# usb.net
KiCad netlist of a schematic drawn in Altium Designer
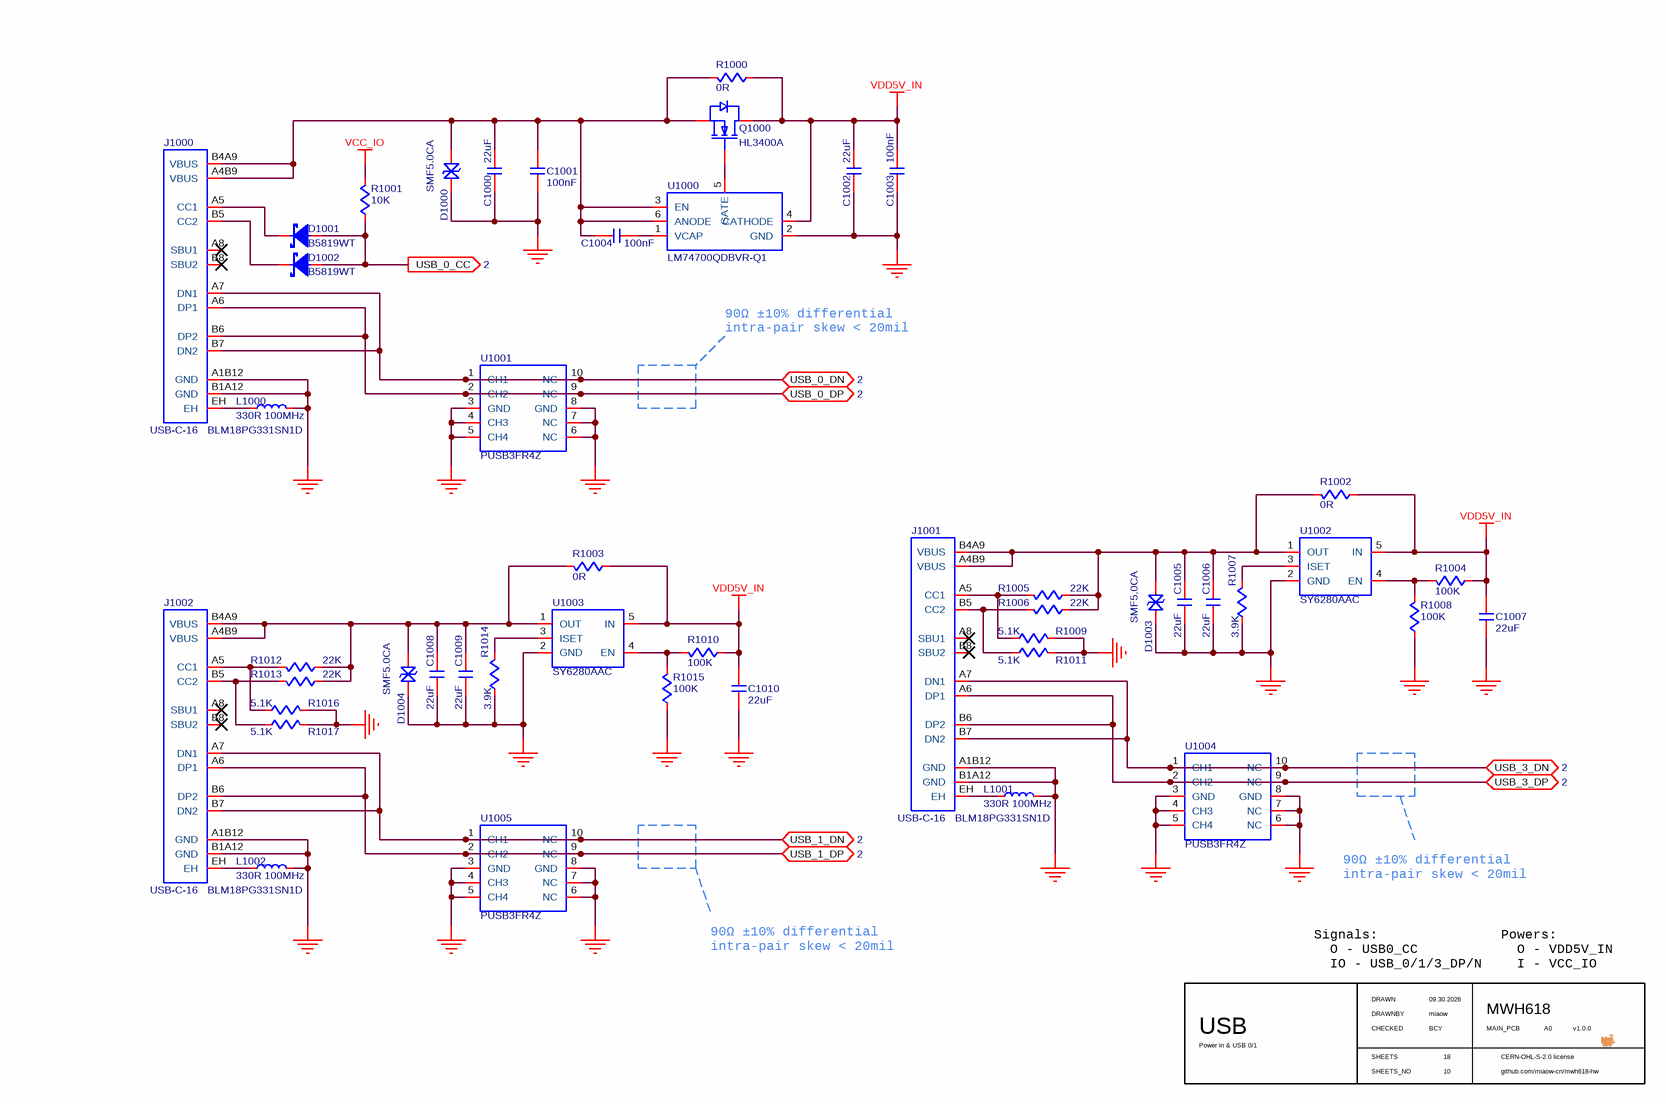
[diagram p0: usb.schdoc]

(export (version "E")
  (design (tool "Eeschema 10.0.6"))
  (components
    (comp (ref "C1000")
      (value "22uF")
      (footprint "mw:C0603")
      (fields (field (name "VOLTAGE") "10V") (field (name "Comment") "C-NOMO"))
      (libsource (lib "mw") (part "C-NOMO"))
    )
    (comp (ref "C1001")
      (value "100nF")
      (footprint "mw:C0402")
      (fields (field (name "VOLTAGE") "50V") (field (name "Comment") "C-NOMO"))
      (libsource (lib "mw") (part "C-NOMO"))
    )
    (comp (ref "C1002")
      (value "22uF")
      (footprint "mw:C0603")
      (fields (field (name "VOLTAGE") "10V") (field (name "Comment") "C-NOMO"))
      (libsource (lib "mw") (part "C-NOMO"))
    )
    (comp (ref "C1003")
      (value "100nF")
      (footprint "mw:C0402")
      (fields (field (name "VOLTAGE") "50V") (field (name "Comment") "C-NOMO"))
      (libsource (lib "mw") (part "C-NOMO"))
    )
    (comp (ref "C1004")
      (value "100nF")
      (footprint "mw:C0402")
      (fields (field (name "VOLTAGE") "50V") (field (name "Comment") "C-NOMO"))
      (libsource (lib "mw") (part "C-NOMO"))
    )
    (comp (ref "C1005")
      (value "22uF")
      (footprint "mw:C0603")
      (fields (field (name "VOLTAGE") "10V") (field (name "Comment") "C-NOMO"))
      (libsource (lib "mw") (part "C-NOMO"))
    )
    (comp (ref "C1006")
      (value "22uF")
      (footprint "mw:C0603")
      (fields (field (name "VOLTAGE") "10V") (field (name "Comment") "C-NOMO"))
      (libsource (lib "mw") (part "C-NOMO"))
    )
    (comp (ref "C1007")
      (value "22uF")
      (footprint "mw:C0603")
      (fields (field (name "VOLTAGE") "10V") (field (name "Comment") "C-NOMO"))
      (libsource (lib "mw") (part "C-NOMO"))
    )
    (comp (ref "C1008")
      (value "22uF")
      (footprint "mw:C0603")
      (fields (field (name "VOLTAGE") "10V") (field (name "Comment") "C-NOMO"))
      (libsource (lib "mw") (part "C-NOMO"))
    )
    (comp (ref "C1009")
      (value "22uF")
      (footprint "mw:C0603")
      (fields (field (name "VOLTAGE") "10V") (field (name "Comment") "C-NOMO"))
      (libsource (lib "mw") (part "C-NOMO"))
    )
    (comp (ref "C1010")
      (value "22uF")
      (footprint "mw:C0603")
      (fields (field (name "VOLTAGE") "10V") (field (name "Comment") "C-NOMO"))
      (libsource (lib "mw") (part "C-NOMO"))
    )
    (comp (ref "D1000")
      (value "SMF5.0CA")
      (footprint "mw:SMF5.0CA")
      (description "TVS/ESD")
      (libsource (lib "mw") (part "SMF5.0CA"))
    )
    (comp (ref "D1001")
      (value "B5819WT")
      (footprint "mw:B5819WT")
      (description "SCHOTTKY")
      (libsource (lib "mw") (part "B5819WT"))
    )
    (comp (ref "D1002")
      (value "B5819WT")
      (footprint "mw:B5819WT")
      (description "SCHOTTKY")
      (libsource (lib "mw") (part "B5819WT"))
    )
    (comp (ref "D1003")
      (value "SMF5.0CA")
      (footprint "mw:SMF5.0CA")
      (description "TVS/ESD")
      (libsource (lib "mw") (part "SMF5.0CA"))
    )
    (comp (ref "D1004")
      (value "SMF5.0CA")
      (footprint "mw:SMF5.0CA")
      (description "TVS/ESD")
      (libsource (lib "mw") (part "SMF5.0CA"))
    )
    (comp (ref "J1000") (value "USB-C-16") (footprint "mw:USB-C-16") (libsource (lib "mw") (part "USB-C-16")))
    (comp (ref "J1001") (value "USB-C-16") (footprint "mw:USB-C-16") (libsource (lib "mw") (part "USB-C-16")))
    (comp (ref "J1002") (value "USB-C-16") (footprint "mw:USB-C-16") (libsource (lib "mw") (part "USB-C-16")))
    (comp (ref "L1000")
      (value "BLM18PG331SN1D")
      (footprint "mw:L0603")
      (fields (field (name "ALTIUM_VALUE") "330R 100MHz") (field (name "PUBLISHER") "Altium Limited"))
      (libsource (lib "mw") (part "L"))
    )
    (comp (ref "L1001")
      (value "BLM18PG331SN1D")
      (footprint "mw:L0603")
      (fields (field (name "ALTIUM_VALUE") "330R 100MHz") (field (name "PUBLISHER") "Altium Limited"))
      (libsource (lib "mw") (part "L"))
    )
    (comp (ref "L1002")
      (value "BLM18PG331SN1D")
      (footprint "mw:L0603")
      (fields (field (name "ALTIUM_VALUE") "330R 100MHz") (field (name "PUBLISHER") "Altium Limited"))
      (libsource (lib "mw") (part "L"))
    )
    (comp (ref "Q1000")
      (value "HL3400A")
      (footprint "mw:HL3400A")
      (description "NMOS")
      (libsource (lib "mw") (part "HL3400A"))
    )
    (comp (ref "R1000")
      (value "0R")
      (footprint "mw:R1206")
      (fields (field (name "Comment") "R"))
      (libsource (lib "mw") (part "R"))
    )
    (comp (ref "R1001")
      (value "10K")
      (footprint "mw:R0402")
      (fields (field (name "Comment") "R"))
      (libsource (lib "mw") (part "R"))
    )
    (comp (ref "R1002")
      (value "0R")
      (footprint "mw:R1206")
      (fields (field (name "Comment") "R"))
      (libsource (lib "mw") (part "R"))
    )
    (comp (ref "R1003")
      (value "0R")
      (footprint "mw:R1206")
      (fields (field (name "Comment") "R"))
      (libsource (lib "mw") (part "R"))
    )
    (comp (ref "R1004")
      (value "100K")
      (footprint "mw:R0402")
      (fields (field (name "Comment") "R"))
      (libsource (lib "mw") (part "R"))
    )
    (comp (ref "R1005")
      (value "22K")
      (footprint "mw:R0402")
      (fields (field (name "Comment") "R"))
      (libsource (lib "mw") (part "R"))
    )
    (comp (ref "R1006")
      (value "22K")
      (footprint "mw:R0402")
      (fields (field (name "Comment") "R"))
      (libsource (lib "mw") (part "R"))
    )
    (comp (ref "R1007")
      (value "3.9K")
      (footprint "mw:R0402")
      (fields (field (name "Comment") "R"))
      (libsource (lib "mw") (part "R"))
    )
    (comp (ref "R1008")
      (value "100K")
      (footprint "mw:R0402")
      (fields (field (name "Comment") "R"))
      (libsource (lib "mw") (part "R"))
    )
    (comp (ref "R1009")
      (value "5.1K")
      (footprint "mw:R0402")
      (fields (field (name "Comment") "R"))
      (libsource (lib "mw") (part "R"))
    )
    (comp (ref "R1010")
      (value "100K")
      (footprint "mw:R0402")
      (fields (field (name "Comment") "R"))
      (libsource (lib "mw") (part "R"))
    )
    (comp (ref "R1011")
      (value "5.1K")
      (footprint "mw:R0402")
      (fields (field (name "Comment") "R"))
      (libsource (lib "mw") (part "R"))
    )
    (comp (ref "R1012")
      (value "22K")
      (footprint "mw:R0402")
      (fields (field (name "Comment") "R"))
      (libsource (lib "mw") (part "R"))
    )
    (comp (ref "R1013")
      (value "22K")
      (footprint "mw:R0402")
      (fields (field (name "Comment") "R"))
      (libsource (lib "mw") (part "R"))
    )
    (comp (ref "R1014")
      (value "3.9K")
      (footprint "mw:R0402")
      (fields (field (name "Comment") "R"))
      (libsource (lib "mw") (part "R"))
    )
    (comp (ref "R1015")
      (value "100K")
      (footprint "mw:R0402")
      (fields (field (name "Comment") "R"))
      (libsource (lib "mw") (part "R"))
    )
    (comp (ref "R1016")
      (value "5.1K")
      (footprint "mw:R0402")
      (fields (field (name "Comment") "R"))
      (libsource (lib "mw") (part "R"))
    )
    (comp (ref "R1017")
      (value "5.1K")
      (footprint "mw:R0402")
      (fields (field (name "Comment") "R"))
      (libsource (lib "mw") (part "R"))
    )
    (comp (ref "U1000")
      (value "LM74700QDBVR-Q1")
      (footprint "mw:LM74700QDBVR-Q1")
      (description "IDEAL DIODE")
      (libsource (lib "mw") (part "LM74700QDBVR-Q1"))
    )
    (comp (ref "U1001")
      (value "PUSB3FR4Z")
      (footprint "mw:PUSB3FR4Z")
      (description "TVS/ESD - USB, HDMI")
      (libsource (lib "mw") (part "PUSB3FR4Z"))
    )
    (comp (ref "U1002")
      (value "SY6280AAC")
      (footprint "mw:SY6280AAC")
      (description "PWR SWITCH")
      (libsource (lib "mw") (part "SY6280AAC"))
    )
    (comp (ref "U1003")
      (value "SY6280AAC")
      (footprint "mw:SY6280AAC")
      (description "PWR SWITCH")
      (libsource (lib "mw") (part "SY6280AAC"))
    )
    (comp (ref "U1004")
      (value "PUSB3FR4Z")
      (footprint "mw:PUSB3FR4Z")
      (description "TVS/ESD - USB, HDMI")
      (libsource (lib "mw") (part "PUSB3FR4Z"))
    )
    (comp (ref "U1005")
      (value "PUSB3FR4Z")
      (footprint "mw:PUSB3FR4Z")
      (description "TVS/ESD - USB, HDMI")
      (libsource (lib "mw") (part "PUSB3FR4Z"))
    )
  )
  (nets
    (net (code "1") (name "/USB_0_CC") (class "Default")
      (node (ref "D1001") (pin "2") (pinfunction "2_2") (pintype "passive"))
      (node (ref "D1002") (pin "2") (pinfunction "2_2") (pintype "passive"))
      (node (ref "R1001") (pin "2") (pinfunction "2_2") (pintype "passive"))
    )
    (net (code "2") (name "/USB_0_DN") (class "Default")
      (node (ref "J1000") (pin "A7") (pinfunction "DN1_A7") (pintype "passive"))
      (node (ref "J1000") (pin "B7") (pinfunction "DN2_B7") (pintype "passive"))
      (node (ref "U1001") (pin "1") (pinfunction "CH1_1") (pintype "passive"))
      (node (ref "U1001") (pin "10") (pinfunction "NC_10") (pintype "passive"))
    )
    (net (code "3") (name "/USB_0_DP") (class "Default")
      (node (ref "J1000") (pin "A6") (pinfunction "DP1_A6") (pintype "passive"))
      (node (ref "J1000") (pin "B6") (pinfunction "DP2_B6") (pintype "passive"))
      (node (ref "U1001") (pin "2") (pinfunction "CH2_2") (pintype "passive"))
      (node (ref "U1001") (pin "9") (pinfunction "NC_9") (pintype "passive"))
    )
    (net (code "4") (name "/USB_1_DN") (class "Default")
      (node (ref "J1002") (pin "A7") (pinfunction "DN1_A7") (pintype "passive"))
      (node (ref "J1002") (pin "B7") (pinfunction "DN2_B7") (pintype "passive"))
      (node (ref "U1005") (pin "1") (pinfunction "CH1_1") (pintype "passive"))
      (node (ref "U1005") (pin "10") (pinfunction "NC_10") (pintype "passive"))
    )
    (net (code "5") (name "/USB_1_DP") (class "Default")
      (node (ref "J1002") (pin "A6") (pinfunction "DP1_A6") (pintype "passive"))
      (node (ref "J1002") (pin "B6") (pinfunction "DP2_B6") (pintype "passive"))
      (node (ref "U1005") (pin "2") (pinfunction "CH2_2") (pintype "passive"))
      (node (ref "U1005") (pin "9") (pinfunction "NC_9") (pintype "passive"))
    )
    (net (code "6") (name "/USB_3_DN") (class "Default")
      (node (ref "J1001") (pin "A7") (pinfunction "DN1_A7") (pintype "passive"))
      (node (ref "J1001") (pin "B7") (pinfunction "DN2_B7") (pintype "passive"))
      (node (ref "U1004") (pin "1") (pinfunction "CH1_1") (pintype "passive"))
      (node (ref "U1004") (pin "10") (pinfunction "NC_10") (pintype "passive"))
    )
    (net (code "7") (name "/USB_3_DP") (class "Default")
      (node (ref "J1001") (pin "A6") (pinfunction "DP1_A6") (pintype "passive"))
      (node (ref "J1001") (pin "B6") (pinfunction "DP2_B6") (pintype "passive"))
      (node (ref "U1004") (pin "2") (pinfunction "CH2_2") (pintype "passive"))
      (node (ref "U1004") (pin "9") (pinfunction "NC_9") (pintype "passive"))
    )
    (net (code "8") (name "GND") (class "Default")
      (node (ref "C1000") (pin "1") (pinfunction "1_1") (pintype "passive"))
      (node (ref "C1001") (pin "2") (pinfunction "2_2") (pintype "passive"))
      (node (ref "C1002") (pin "1") (pinfunction "1_1") (pintype "passive"))
      (node (ref "C1003") (pin "2") (pinfunction "2_2") (pintype "passive"))
      (node (ref "C1005") (pin "1") (pinfunction "1_1") (pintype "passive"))
      (node (ref "C1006") (pin "1") (pinfunction "1_1") (pintype "passive"))
      (node (ref "C1007") (pin "2") (pinfunction "2_2") (pintype "passive"))
      (node (ref "C1008") (pin "1") (pinfunction "1_1") (pintype "passive"))
      (node (ref "C1009") (pin "1") (pinfunction "1_1") (pintype "passive"))
      (node (ref "C1010") (pin "2") (pinfunction "2_2") (pintype "passive"))
      (node (ref "D1000") (pin "1") (pinfunction "1_1") (pintype "passive"))
      (node (ref "D1003") (pin "1") (pinfunction "1_1") (pintype "passive"))
      (node (ref "D1004") (pin "1") (pinfunction "1_1") (pintype "passive"))
      (node (ref "J1000") (pin "A1B12") (pinfunction "GND_A1B12") (pintype "passive"))
      (node (ref "J1000") (pin "B1A12") (pinfunction "GND_B1A12") (pintype "passive"))
      (node (ref "J1001") (pin "A1B12") (pinfunction "GND_A1B12") (pintype "passive"))
      (node (ref "J1001") (pin "B1A12") (pinfunction "GND_B1A12") (pintype "passive"))
      (node (ref "J1002") (pin "A1B12") (pinfunction "GND_A1B12") (pintype "passive"))
      (node (ref "J1002") (pin "B1A12") (pinfunction "GND_B1A12") (pintype "passive"))
      (node (ref "L1000") (pin "2") (pinfunction "2_2") (pintype "passive"))
      (node (ref "L1001") (pin "2") (pinfunction "2_2") (pintype "passive"))
      (node (ref "L1002") (pin "2") (pinfunction "2_2") (pintype "passive"))
      (node (ref "R1007") (pin "2") (pinfunction "2_2") (pintype "passive"))
      (node (ref "R1008") (pin "2") (pinfunction "2_2") (pintype "passive"))
      (node (ref "R1009") (pin "1") (pinfunction "1_1") (pintype "passive"))
      (node (ref "R1011") (pin "1") (pinfunction "1_1") (pintype "passive"))
      (node (ref "R1014") (pin "2") (pinfunction "2_2") (pintype "passive"))
      (node (ref "R1015") (pin "2") (pinfunction "2_2") (pintype "passive"))
      (node (ref "R1016") (pin "1") (pinfunction "1_1") (pintype "passive"))
      (node (ref "R1017") (pin "1") (pinfunction "1_1") (pintype "passive"))
      (node (ref "U1000") (pin "2") (pinfunction "GND_2") (pintype "passive"))
      (node (ref "U1001") (pin "3") (pinfunction "GND_3") (pintype "passive"))
      (node (ref "U1001") (pin "4") (pinfunction "CH3_4") (pintype "passive"))
      (node (ref "U1001") (pin "5") (pinfunction "CH4_5") (pintype "passive"))
      (node (ref "U1001") (pin "6") (pinfunction "NC_6") (pintype "passive"))
      (node (ref "U1001") (pin "7") (pinfunction "NC_7") (pintype "passive"))
      (node (ref "U1001") (pin "8") (pinfunction "GND_8") (pintype "passive"))
      (node (ref "U1002") (pin "2") (pinfunction "GND_2") (pintype "passive"))
      (node (ref "U1003") (pin "2") (pinfunction "GND_2") (pintype "passive"))
      (node (ref "U1004") (pin "3") (pinfunction "GND_3") (pintype "passive"))
      (node (ref "U1004") (pin "4") (pinfunction "CH3_4") (pintype "passive"))
      (node (ref "U1004") (pin "5") (pinfunction "CH4_5") (pintype "passive"))
      (node (ref "U1004") (pin "6") (pinfunction "NC_6") (pintype "passive"))
      (node (ref "U1004") (pin "7") (pinfunction "NC_7") (pintype "passive"))
      (node (ref "U1004") (pin "8") (pinfunction "GND_8") (pintype "passive"))
      (node (ref "U1005") (pin "3") (pinfunction "GND_3") (pintype "passive"))
      (node (ref "U1005") (pin "4") (pinfunction "CH3_4") (pintype "passive"))
      (node (ref "U1005") (pin "5") (pinfunction "CH4_5") (pintype "passive"))
      (node (ref "U1005") (pin "6") (pinfunction "NC_6") (pintype "passive"))
      (node (ref "U1005") (pin "7") (pinfunction "NC_7") (pintype "passive"))
      (node (ref "U1005") (pin "8") (pinfunction "GND_8") (pintype "passive"))
    )
    (net (code "9") (name "Net-(J1000-CC1)") (class "Default")
      (node (ref "D1001") (pin "1") (pinfunction "1_1") (pintype "passive"))
      (node (ref "J1000") (pin "A5") (pinfunction "CC1_A5") (pintype "passive"))
    )
    (net (code "10") (name "Net-(J1000-CC2)") (class "Default")
      (node (ref "D1002") (pin "1") (pinfunction "1_1") (pintype "passive"))
      (node (ref "J1000") (pin "B5") (pinfunction "CC2_B5") (pintype "passive"))
    )
    (net (code "11") (name "Net-(J1000-PadEH)") (class "Default")
      (node (ref "J1000") (pin "EH") (pinfunction "EH_EH") (pintype "passive"))
      (node (ref "L1000") (pin "1") (pinfunction "1_1") (pintype "passive"))
    )
    (net (code "12") (name "Net-(J1001-CC1)") (class "Default")
      (node (ref "J1001") (pin "A5") (pinfunction "CC1_A5") (pintype "passive"))
      (node (ref "R1005") (pin "1") (pinfunction "1_1") (pintype "passive"))
      (node (ref "R1009") (pin "2") (pinfunction "2_2") (pintype "passive"))
    )
    (net (code "13") (name "Net-(J1001-CC2)") (class "Default")
      (node (ref "J1001") (pin "B5") (pinfunction "CC2_B5") (pintype "passive"))
      (node (ref "R1006") (pin "1") (pinfunction "1_1") (pintype "passive"))
      (node (ref "R1011") (pin "2") (pinfunction "2_2") (pintype "passive"))
    )
    (net (code "14") (name "Net-(J1001-PadEH)") (class "Default")
      (node (ref "J1001") (pin "EH") (pinfunction "EH_EH") (pintype "passive"))
      (node (ref "L1001") (pin "1") (pinfunction "1_1") (pintype "passive"))
    )
    (net (code "15") (name "Net-(J1002-CC1)") (class "Default")
      (node (ref "J1002") (pin "A5") (pinfunction "CC1_A5") (pintype "passive"))
      (node (ref "R1012") (pin "1") (pinfunction "1_1") (pintype "passive"))
      (node (ref "R1016") (pin "2") (pinfunction "2_2") (pintype "passive"))
    )
    (net (code "16") (name "Net-(J1002-CC2)") (class "Default")
      (node (ref "J1002") (pin "B5") (pinfunction "CC2_B5") (pintype "passive"))
      (node (ref "R1013") (pin "1") (pinfunction "1_1") (pintype "passive"))
      (node (ref "R1017") (pin "2") (pinfunction "2_2") (pintype "passive"))
    )
    (net (code "17") (name "Net-(J1002-PadEH)") (class "Default")
      (node (ref "J1002") (pin "EH") (pinfunction "EH_EH") (pintype "passive"))
      (node (ref "L1002") (pin "1") (pinfunction "1_1") (pintype "passive"))
    )
    (net (code "18") (name "Net-(U1000-ANODE)") (class "Default")
      (node (ref "C1000") (pin "2") (pinfunction "2_2") (pintype "passive"))
      (node (ref "C1001") (pin "1") (pinfunction "1_1") (pintype "passive"))
      (node (ref "C1004") (pin "2") (pinfunction "2_2") (pintype "passive"))
      (node (ref "D1000") (pin "2") (pinfunction "2_2") (pintype "passive"))
      (node (ref "J1000") (pin "A4B9") (pinfunction "VBUS_A4B9") (pintype "passive"))
      (node (ref "J1000") (pin "B4A9") (pinfunction "VBUS_B4A9") (pintype "passive"))
      (node (ref "Q1000") (pin "S") (pinfunction "S_S") (pintype "passive"))
      (node (ref "R1000") (pin "1") (pinfunction "1_1") (pintype "passive"))
      (node (ref "U1000") (pin "3") (pinfunction "EN_3") (pintype "passive"))
      (node (ref "U1000") (pin "6") (pinfunction "ANODE_6") (pintype "passive"))
    )
    (net (code "19") (name "Net-(U1000-GATE)") (class "Default")
      (node (ref "Q1000") (pin "G") (pinfunction "G_G") (pintype "passive"))
      (node (ref "U1000") (pin "5") (pinfunction "GATE_5") (pintype "passive"))
    )
    (net (code "20") (name "Net-(U1000-VCAP)") (class "Default")
      (node (ref "C1004") (pin "1") (pinfunction "1_1") (pintype "passive"))
      (node (ref "U1000") (pin "1") (pinfunction "VCAP_1") (pintype "passive"))
    )
    (net (code "21") (name "Net-(U1002-EN)") (class "Default")
      (node (ref "R1004") (pin "1") (pinfunction "1_1") (pintype "passive"))
      (node (ref "R1008") (pin "1") (pinfunction "1_1") (pintype "passive"))
      (node (ref "U1002") (pin "4") (pinfunction "EN_4") (pintype "passive"))
    )
    (net (code "22") (name "Net-(U1002-ISET)") (class "Default")
      (node (ref "R1007") (pin "1") (pinfunction "1_1") (pintype "passive"))
      (node (ref "U1002") (pin "3") (pinfunction "ISET_3") (pintype "passive"))
    )
    (net (code "23") (name "Net-(U1002-OUT)") (class "Default")
      (node (ref "C1005") (pin "2") (pinfunction "2_2") (pintype "passive"))
      (node (ref "C1006") (pin "2") (pinfunction "2_2") (pintype "passive"))
      (node (ref "D1003") (pin "2") (pinfunction "2_2") (pintype "passive"))
      (node (ref "J1001") (pin "A4B9") (pinfunction "VBUS_A4B9") (pintype "passive"))
      (node (ref "J1001") (pin "B4A9") (pinfunction "VBUS_B4A9") (pintype "passive"))
      (node (ref "R1002") (pin "1") (pinfunction "1_1") (pintype "passive"))
      (node (ref "R1005") (pin "2") (pinfunction "2_2") (pintype "passive"))
      (node (ref "R1006") (pin "2") (pinfunction "2_2") (pintype "passive"))
      (node (ref "U1002") (pin "1") (pinfunction "OUT_1") (pintype "passive"))
    )
    (net (code "24") (name "Net-(U1003-EN)") (class "Default")
      (node (ref "R1010") (pin "1") (pinfunction "1_1") (pintype "passive"))
      (node (ref "R1015") (pin "1") (pinfunction "1_1") (pintype "passive"))
      (node (ref "U1003") (pin "4") (pinfunction "EN_4") (pintype "passive"))
    )
    (net (code "25") (name "Net-(U1003-ISET)") (class "Default")
      (node (ref "R1014") (pin "1") (pinfunction "1_1") (pintype "passive"))
      (node (ref "U1003") (pin "3") (pinfunction "ISET_3") (pintype "passive"))
    )
    (net (code "26") (name "Net-(U1003-OUT)") (class "Default")
      (node (ref "C1008") (pin "2") (pinfunction "2_2") (pintype "passive"))
      (node (ref "C1009") (pin "2") (pinfunction "2_2") (pintype "passive"))
      (node (ref "D1004") (pin "2") (pinfunction "2_2") (pintype "passive"))
      (node (ref "J1002") (pin "A4B9") (pinfunction "VBUS_A4B9") (pintype "passive"))
      (node (ref "J1002") (pin "B4A9") (pinfunction "VBUS_B4A9") (pintype "passive"))
      (node (ref "R1003") (pin "1") (pinfunction "1_1") (pintype "passive"))
      (node (ref "R1012") (pin "2") (pinfunction "2_2") (pintype "passive"))
      (node (ref "R1013") (pin "2") (pinfunction "2_2") (pintype "passive"))
      (node (ref "U1003") (pin "1") (pinfunction "OUT_1") (pintype "passive"))
    )
    (net (code "27") (name "VCC_IO") (class "Default")
      (node (ref "R1001") (pin "1") (pinfunction "1_1") (pintype "passive"))
    )
    (net (code "28") (name "VDD5V_IN") (class "Default")
      (node (ref "C1002") (pin "2") (pinfunction "2_2") (pintype "passive"))
      (node (ref "C1003") (pin "1") (pinfunction "1_1") (pintype "passive"))
      (node (ref "C1007") (pin "1") (pinfunction "1_1") (pintype "passive"))
      (node (ref "C1010") (pin "1") (pinfunction "1_1") (pintype "passive"))
      (node (ref "Q1000") (pin "D") (pinfunction "D_D") (pintype "passive"))
      (node (ref "R1000") (pin "2") (pinfunction "2_2") (pintype "passive"))
      (node (ref "R1002") (pin "2") (pinfunction "2_2") (pintype "passive"))
      (node (ref "R1003") (pin "2") (pinfunction "2_2") (pintype "passive"))
      (node (ref "R1004") (pin "2") (pinfunction "2_2") (pintype "passive"))
      (node (ref "R1010") (pin "2") (pinfunction "2_2") (pintype "passive"))
      (node (ref "U1000") (pin "4") (pinfunction "CATHODE_4") (pintype "passive"))
      (node (ref "U1002") (pin "5") (pinfunction "IN_5") (pintype "passive"))
      (node (ref "U1003") (pin "5") (pinfunction "IN_5") (pintype "passive"))
    )
    (net (code "29") (name "unconnected-(J1000-SBU1-PadA8)") (class "Default")
      (node (ref "J1000") (pin "A8") (pinfunction "SBU1_A8") (pintype "passive+no_connect"))
    )
    (net (code "30") (name "unconnected-(J1000-SBU2-PadB8)") (class "Default")
      (node (ref "J1000") (pin "B8") (pinfunction "SBU2_B8") (pintype "passive+no_connect"))
    )
    (net (code "31") (name "unconnected-(J1001-SBU1-PadA8)") (class "Default")
      (node (ref "J1001") (pin "A8") (pinfunction "SBU1_A8") (pintype "passive+no_connect"))
    )
    (net (code "32") (name "unconnected-(J1001-SBU2-PadB8)") (class "Default")
      (node (ref "J1001") (pin "B8") (pinfunction "SBU2_B8") (pintype "passive+no_connect"))
    )
    (net (code "33") (name "unconnected-(J1002-SBU1-PadA8)") (class "Default")
      (node (ref "J1002") (pin "A8") (pinfunction "SBU1_A8") (pintype "passive+no_connect"))
    )
    (net (code "34") (name "unconnected-(J1002-SBU2-PadB8)") (class "Default")
      (node (ref "J1002") (pin "B8") (pinfunction "SBU2_B8") (pintype "passive+no_connect"))
    )
  )
)
